# slang-lsm6dsl-ukazovak.net
KiCad netlist of a schematic drawn in EAGLE
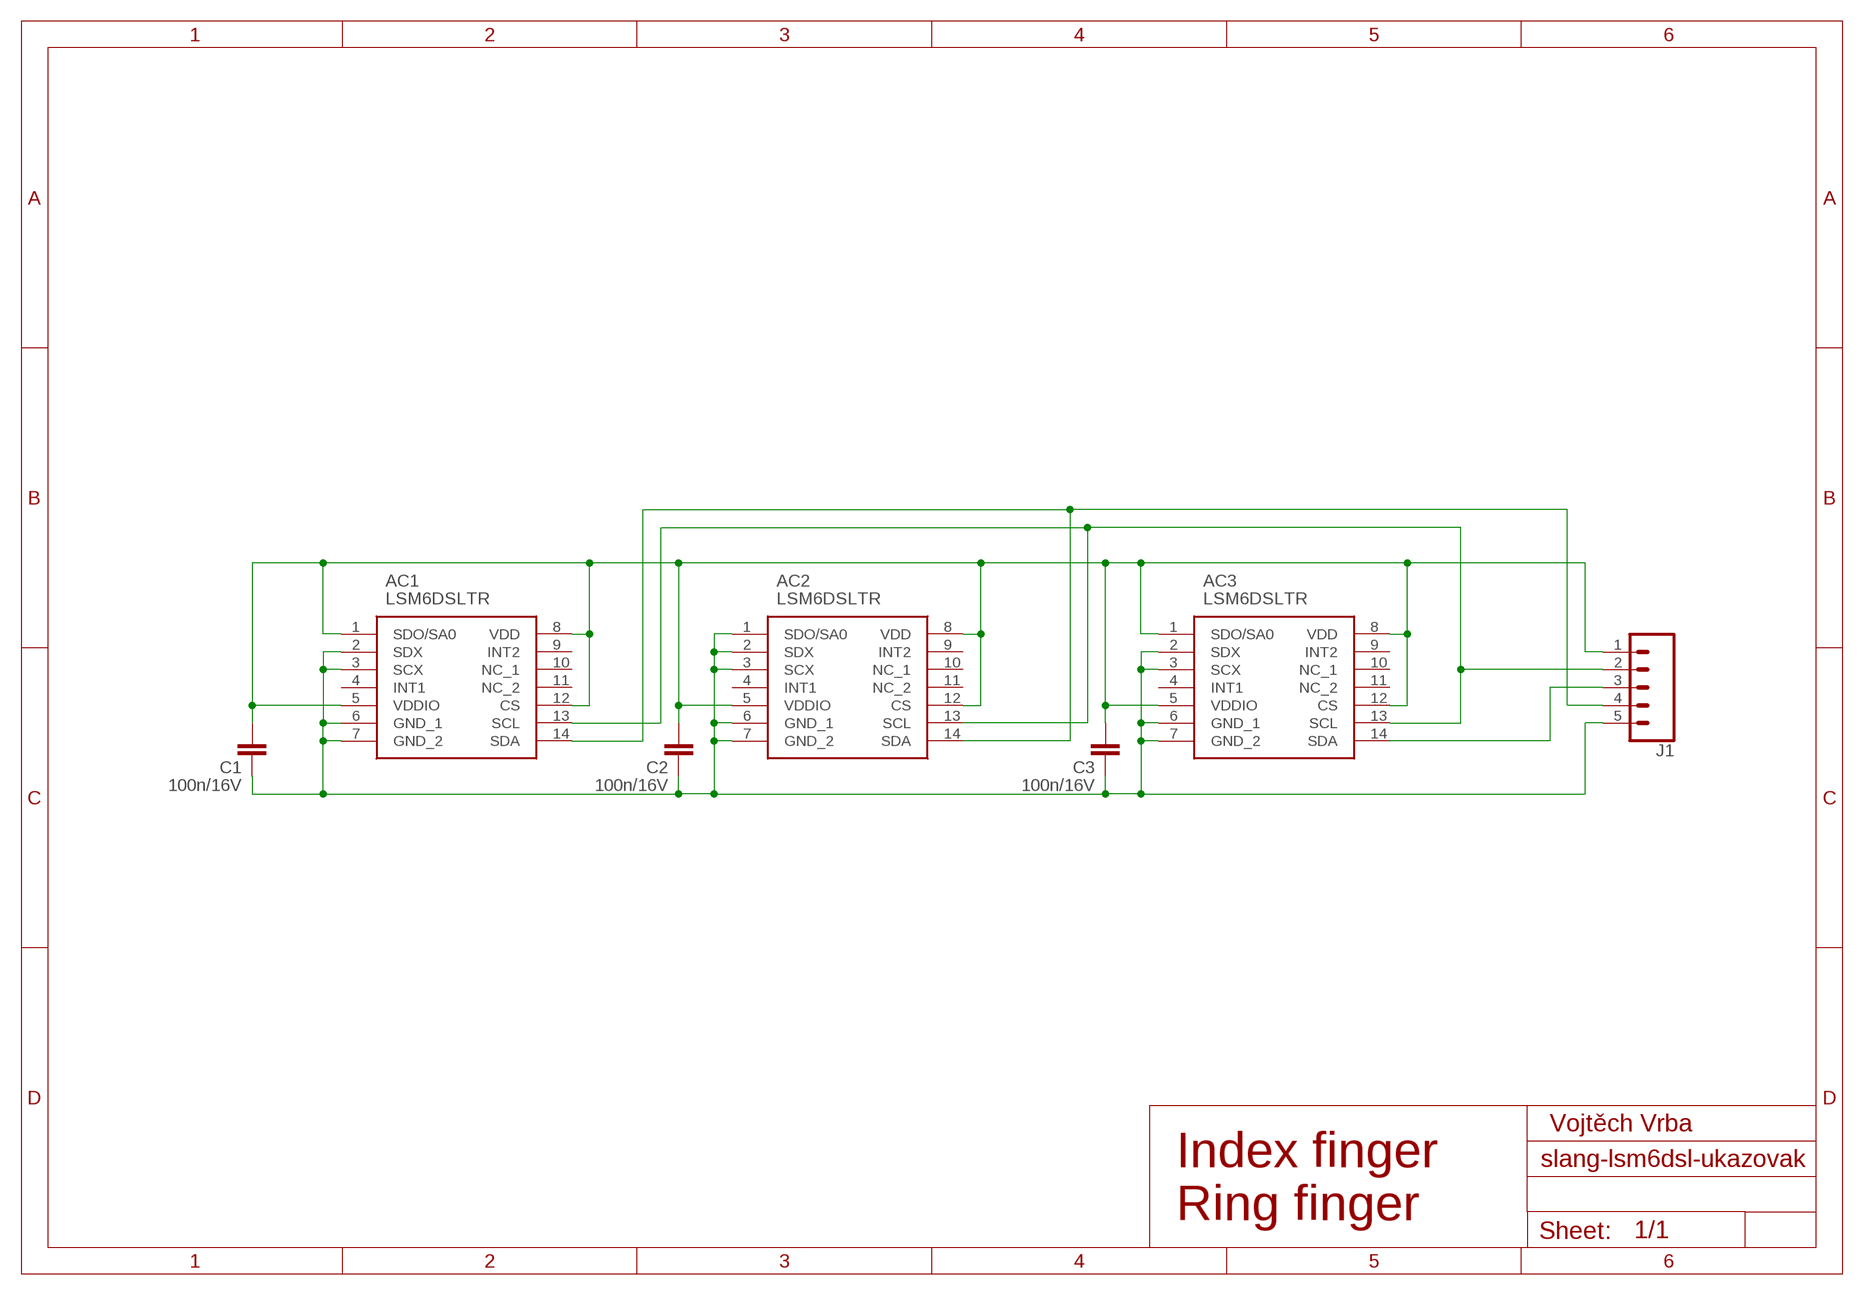
[diagram p0: schematic, sheet 1]

(export (version "E")
  (design (tool "Eeschema 10.0.6"))
  (components
    (comp (ref "AC1")
      (value "LSM6DSLTR")
      (footprint "eagle-import:LGA-14(2.5X3X0.86)")
      (fields (field (name "RS_PART_NUMBER") "1639811P"))
      (libsource (lib "eagle-import") (part "LSM6DSLTR"))
    )
    (comp (ref "AC2")
      (value "LSM6DSLTR")
      (footprint "eagle-import:LGA-14(2.5X3X0.86)")
      (fields (field (name "RS_PART_NUMBER") "1639811P"))
      (libsource (lib "eagle-import") (part "LSM6DSLTR"))
    )
    (comp (ref "AC3")
      (value "LSM6DSLTR")
      (footprint "eagle-import:LGA-14(2.5X3X0.86)")
      (fields (field (name "RS_PART_NUMBER") "1639811P"))
      (libsource (lib "eagle-import") (part "LSM6DSLTR"))
    )
    (comp (ref "C1")
      (value "100n/16V")
      (footprint "eagle-import:C0603")
      (libsource (lib "eagle-import") (part "C-EUC0603"))
    )
    (comp (ref "C2")
      (value "100n/16V")
      (footprint "eagle-import:C0603")
      (libsource (lib "eagle-import") (part "C-EUC0603"))
    )
    (comp (ref "C3")
      (value "100n/16V")
      (footprint "eagle-import:C0603")
      (libsource (lib "eagle-import") (part "C-EUC0603"))
    )
    (comp (ref "J1")
      (value "CONN_051.27MM")
      (footprint "eagle-import:1X05_1.27MM")
      (libsource (lib "eagle-import") (part "CONN_051.27MM"))
    )
  )
  (nets
    (net (code "1") (name "Net-(AC1-CS)") (class "Default")
      (node (ref "AC1") (pin "1") (pinfunction "SDO/SA0_1") (pintype "bidirectional"))
      (node (ref "AC1") (pin "12") (pinfunction "CS_12") (pintype "bidirectional"))
      (node (ref "AC1") (pin "5") (pinfunction "VDDIO_5") (pintype "bidirectional"))
      (node (ref "AC1") (pin "8") (pinfunction "VDD_8") (pintype "bidirectional"))
      (node (ref "AC2") (pin "12") (pinfunction "CS_12") (pintype "bidirectional"))
      (node (ref "AC2") (pin "5") (pinfunction "VDDIO_5") (pintype "bidirectional"))
      (node (ref "AC2") (pin "8") (pinfunction "VDD_8") (pintype "bidirectional"))
      (node (ref "AC3") (pin "1") (pinfunction "SDO/SA0_1") (pintype "bidirectional"))
      (node (ref "AC3") (pin "12") (pinfunction "CS_12") (pintype "bidirectional"))
      (node (ref "AC3") (pin "5") (pinfunction "VDDIO_5") (pintype "bidirectional"))
      (node (ref "AC3") (pin "8") (pinfunction "VDD_8") (pintype "bidirectional"))
      (node (ref "C1") (pin "2") (pinfunction "2_2") (pintype "passive"))
      (node (ref "C2") (pin "2") (pinfunction "2_2") (pintype "passive"))
      (node (ref "C3") (pin "2") (pinfunction "2_2") (pintype "passive"))
      (node (ref "J1") (pin "1") (pinfunction "1_1") (pintype "passive"))
    )
    (net (code "2") (name "Net-(AC1-GND_1)") (class "Default")
      (node (ref "AC1") (pin "2") (pinfunction "SDX_2") (pintype "bidirectional"))
      (node (ref "AC1") (pin "3") (pinfunction "SCX_3") (pintype "bidirectional"))
      (node (ref "AC1") (pin "6") (pinfunction "GND_1_6") (pintype "bidirectional"))
      (node (ref "AC1") (pin "7") (pinfunction "GND_2_7") (pintype "bidirectional"))
      (node (ref "AC2") (pin "1") (pinfunction "SDO/SA0_1") (pintype "bidirectional"))
      (node (ref "AC2") (pin "2") (pinfunction "SDX_2") (pintype "bidirectional"))
      (node (ref "AC2") (pin "3") (pinfunction "SCX_3") (pintype "bidirectional"))
      (node (ref "AC2") (pin "6") (pinfunction "GND_1_6") (pintype "bidirectional"))
      (node (ref "AC2") (pin "7") (pinfunction "GND_2_7") (pintype "bidirectional"))
      (node (ref "AC3") (pin "2") (pinfunction "SDX_2") (pintype "bidirectional"))
      (node (ref "AC3") (pin "3") (pinfunction "SCX_3") (pintype "bidirectional"))
      (node (ref "AC3") (pin "6") (pinfunction "GND_1_6") (pintype "bidirectional"))
      (node (ref "AC3") (pin "7") (pinfunction "GND_2_7") (pintype "bidirectional"))
      (node (ref "C1") (pin "1") (pinfunction "1_1") (pintype "passive"))
      (node (ref "C2") (pin "1") (pinfunction "1_1") (pintype "passive"))
      (node (ref "C3") (pin "1") (pinfunction "1_1") (pintype "passive"))
      (node (ref "J1") (pin "5") (pinfunction "5_5") (pintype "passive"))
    )
    (net (code "3") (name "Net-(AC1-SCL)") (class "Default")
      (node (ref "AC1") (pin "13") (pinfunction "SCL_13") (pintype "bidirectional"))
      (node (ref "AC2") (pin "13") (pinfunction "SCL_13") (pintype "bidirectional"))
      (node (ref "AC3") (pin "13") (pinfunction "SCL_13") (pintype "bidirectional"))
      (node (ref "J1") (pin "2") (pinfunction "2_2") (pintype "passive"))
    )
    (net (code "4") (name "Net-(AC1-SDA)") (class "Default")
      (node (ref "AC1") (pin "14") (pinfunction "SDA_14") (pintype "bidirectional"))
      (node (ref "AC2") (pin "14") (pinfunction "SDA_14") (pintype "bidirectional"))
      (node (ref "J1") (pin "4") (pinfunction "4_4") (pintype "passive"))
    )
    (net (code "5") (name "Net-(AC3-SDA)") (class "Default")
      (node (ref "AC3") (pin "14") (pinfunction "SDA_14") (pintype "bidirectional"))
      (node (ref "J1") (pin "3") (pinfunction "3_3") (pintype "passive"))
    )
    (net (code "6") (name "unconnected-(AC1-INT1-Pad4)") (class "Default")
      (node (ref "AC1") (pin "4") (pinfunction "INT1_4") (pintype "bidirectional"))
    )
    (net (code "7") (name "unconnected-(AC1-INT2-Pad9)") (class "Default")
      (node (ref "AC1") (pin "9") (pinfunction "INT2_9") (pintype "bidirectional"))
    )
    (net (code "8") (name "unconnected-(AC1-NC_1-Pad10)") (class "Default")
      (node (ref "AC1") (pin "10") (pinfunction "NC_1_10") (pintype "bidirectional"))
    )
    (net (code "9") (name "unconnected-(AC1-NC_2-Pad11)") (class "Default")
      (node (ref "AC1") (pin "11") (pinfunction "NC_2_11") (pintype "bidirectional"))
    )
    (net (code "10") (name "unconnected-(AC2-INT1-Pad4)") (class "Default")
      (node (ref "AC2") (pin "4") (pinfunction "INT1_4") (pintype "bidirectional"))
    )
    (net (code "11") (name "unconnected-(AC2-INT2-Pad9)") (class "Default")
      (node (ref "AC2") (pin "9") (pinfunction "INT2_9") (pintype "bidirectional"))
    )
    (net (code "12") (name "unconnected-(AC2-NC_1-Pad10)") (class "Default")
      (node (ref "AC2") (pin "10") (pinfunction "NC_1_10") (pintype "bidirectional"))
    )
    (net (code "13") (name "unconnected-(AC2-NC_2-Pad11)") (class "Default")
      (node (ref "AC2") (pin "11") (pinfunction "NC_2_11") (pintype "bidirectional"))
    )
    (net (code "14") (name "unconnected-(AC3-INT1-Pad4)") (class "Default")
      (node (ref "AC3") (pin "4") (pinfunction "INT1_4") (pintype "bidirectional"))
    )
    (net (code "15") (name "unconnected-(AC3-INT2-Pad9)") (class "Default")
      (node (ref "AC3") (pin "9") (pinfunction "INT2_9") (pintype "bidirectional"))
    )
    (net (code "16") (name "unconnected-(AC3-NC_1-Pad10)") (class "Default")
      (node (ref "AC3") (pin "10") (pinfunction "NC_1_10") (pintype "bidirectional"))
    )
    (net (code "17") (name "unconnected-(AC3-NC_2-Pad11)") (class "Default")
      (node (ref "AC3") (pin "11") (pinfunction "NC_2_11") (pintype "bidirectional"))
    )
  )
)
